# Wireless.net
KiCad netlist of a schematic drawn in EAGLE
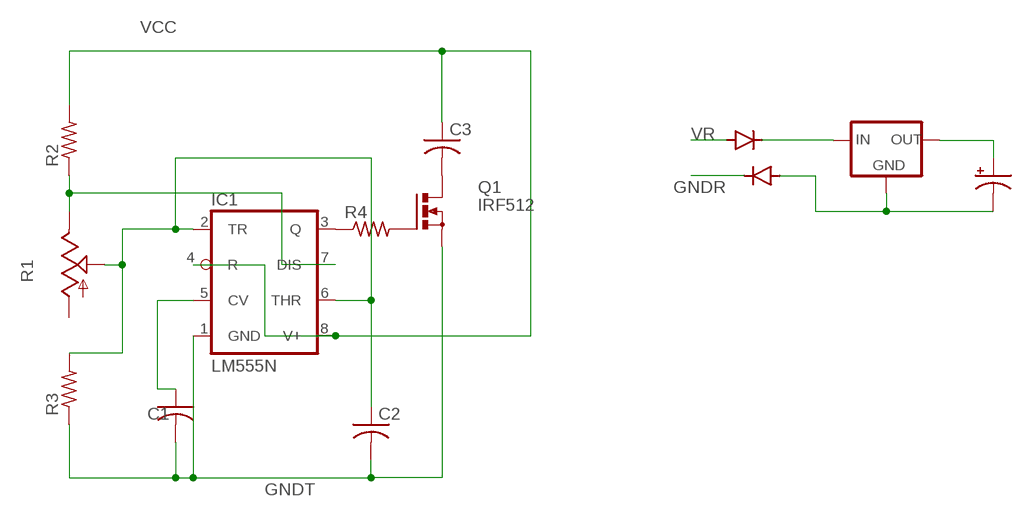
[diagram p0: schematic, sheet 1]

(export (version "E")
  (design (tool "Eeschema 10.0.6"))
  (components
    (comp (ref "C1")
      (value "C-US050-025X075")
      (footprint "eagle-import:C050-025X075")
      (libsource (lib "eagle-import") (part "C-US050-025X075"))
    )
    (comp (ref "C2")
      (value "C-US050-025X075")
      (footprint "eagle-import:C050-025X075")
      (libsource (lib "eagle-import") (part "C-US050-025X075"))
    )
    (comp (ref "C3")
      (value "C-US050-025X075")
      (footprint "eagle-import:C050-025X075")
      (libsource (lib "eagle-import") (part "C-US050-025X075"))
    )
    (comp (ref "C4")
      (value "CPOL-USE2.5-6")
      (footprint "eagle-import:E2,5-6")
      (libsource (lib "eagle-import") (part "CPOL-USE2.5-6"))
    )
    (comp (ref "D1")
      (value "1N4004")
      (footprint "eagle-import:DO41-10")
      (libsource (lib "eagle-import") (part "1N4004"))
    )
    (comp (ref "D2")
      (value "1N4004")
      (footprint "eagle-import:DO41-10")
      (libsource (lib "eagle-import") (part "1N4004"))
    )
    (comp (ref "IC1")
      (value "LM555N")
      (footprint "eagle-import:DIL08-ROUND")
      (libsource (lib "eagle-import") (part "555NLM"))
    )
    (comp (ref "IC2")
      (value "78XXS")
      (footprint "eagle-import:78XXS")
      (libsource (lib "eagle-import") (part "78XXS"))
    )
    (comp (ref "Q1")
      (value "IRF512")
      (footprint "eagle-import:TO220BV")
      (libsource (lib "eagle-import") (part "IRF512"))
    )
    (comp (ref "R1")
      (value "TRIM_US-CA6V")
      (footprint "eagle-import:CA6V")
      (libsource (lib "eagle-import") (part "TRIM_US-CA6V"))
    )
    (comp (ref "R2")
      (value "R-US_0207/10")
      (footprint "eagle-import:0207_10")
      (libsource (lib "eagle-import") (part "R-US_0207/10"))
    )
    (comp (ref "R3")
      (value "R-US_0207/10")
      (footprint "eagle-import:0207_10")
      (libsource (lib "eagle-import") (part "R-US_0207/10"))
    )
    (comp (ref "R4")
      (value "R-US_0207/10")
      (footprint "eagle-import:0207_10")
      (libsource (lib "eagle-import") (part "R-US_0207/10"))
    )
  )
  (nets
    (net (code "1") (name "/GNDR") (class "Default")
      (node (ref "D2") (pin "C") (pinfunction "C_C") (pintype "passive"))
    )
    (net (code "2") (name "/GNDT") (class "Default")
      (node (ref "C1") (pin "2") (pinfunction "2_2") (pintype "passive"))
      (node (ref "C2") (pin "2") (pinfunction "2_2") (pintype "passive"))
      (node (ref "IC1") (pin "1") (pinfunction "GND_1") (pintype "power_in"))
      (node (ref "Q1") (pin "S") (pinfunction "S_S") (pintype "passive"))
      (node (ref "R3") (pin "1") (pinfunction "1_1") (pintype "passive"))
    )
    (net (code "3") (name "/VCC") (class "Default")
      (node (ref "C3") (pin "1") (pinfunction "1_1") (pintype "passive"))
      (node (ref "IC1") (pin "4") (pinfunction "R_4") (pintype "input"))
      (node (ref "IC1") (pin "8") (pinfunction "V+_8") (pintype "power_in"))
      (node (ref "R2") (pin "2") (pinfunction "2_2") (pintype "passive"))
    )
    (net (code "4") (name "/VR") (class "Default")
      (node (ref "D1") (pin "A") (pinfunction "A_A") (pintype "passive"))
    )
    (net (code "5") (name "Net-(C3-Pad2)") (class "Default")
      (node (ref "C3") (pin "2") (pinfunction "2_2") (pintype "passive"))
      (node (ref "Q1") (pin "D") (pinfunction "D_D") (pintype "passive"))
    )
    (net (code "6") (name "Net-(C4-Pad+)") (class "Default")
      (node (ref "C4") (pin "+") (pinfunction "+_+") (pintype "passive"))
      (node (ref "IC2") (pin "OUT") (pinfunction "OUT_OUT") (pintype "passive"))
    )
    (net (code "7") (name "Net-(C4-Pad-)") (class "Default")
      (node (ref "C4") (pin "-") (pinfunction "-_-") (pintype "passive"))
      (node (ref "D2") (pin "A") (pinfunction "A_A") (pintype "passive"))
      (node (ref "IC2") (pin "GND") (pinfunction "GND_GND") (pintype "input"))
    )
    (net (code "8") (name "Net-(D1-PadC)") (class "Default")
      (node (ref "D1") (pin "C") (pinfunction "C_C") (pintype "passive"))
      (node (ref "IC2") (pin "IN") (pinfunction "IN_IN") (pintype "input"))
    )
    (net (code "9") (name "Net-(IC1-CV)") (class "Default")
      (node (ref "C1") (pin "1") (pinfunction "1_1") (pintype "passive"))
      (node (ref "IC1") (pin "5") (pinfunction "CV_5") (pintype "input"))
    )
    (net (code "10") (name "Net-(IC1-DIS)") (class "Default")
      (node (ref "IC1") (pin "7") (pinfunction "DIS_7") (pintype "input"))
      (node (ref "R1") (pin "E") (pinfunction "E_E") (pintype "passive"))
      (node (ref "R2") (pin "1") (pinfunction "1_1") (pintype "passive"))
    )
    (net (code "11") (name "Net-(IC1-Q)") (class "Default")
      (node (ref "IC1") (pin "3") (pinfunction "Q_3") (pintype "output"))
      (node (ref "R4") (pin "1") (pinfunction "1_1") (pintype "passive"))
    )
    (net (code "12") (name "Net-(IC1-THR)") (class "Default")
      (node (ref "C2") (pin "1") (pinfunction "1_1") (pintype "passive"))
      (node (ref "IC1") (pin "2") (pinfunction "TR_2") (pintype "input"))
      (node (ref "IC1") (pin "6") (pinfunction "THR_6") (pintype "input"))
      (node (ref "R1") (pin "S") (pinfunction "S_S") (pintype "passive"))
      (node (ref "R3") (pin "2") (pinfunction "2_2") (pintype "passive"))
    )
    (net (code "13") (name "Net-(Q1-PadG)") (class "Default")
      (node (ref "Q1") (pin "G") (pinfunction "G_G") (pintype "passive"))
      (node (ref "R4") (pin "2") (pinfunction "2_2") (pintype "passive"))
    )
    (net (code "14") (name "unconnected-(R1-PadA)") (class "Default")
      (node (ref "R1") (pin "A") (pinfunction "A_A") (pintype "passive"))
    )
  )
)
